# Switched_I2C.net
KiCad netlist of a schematic drawn in EAGLE
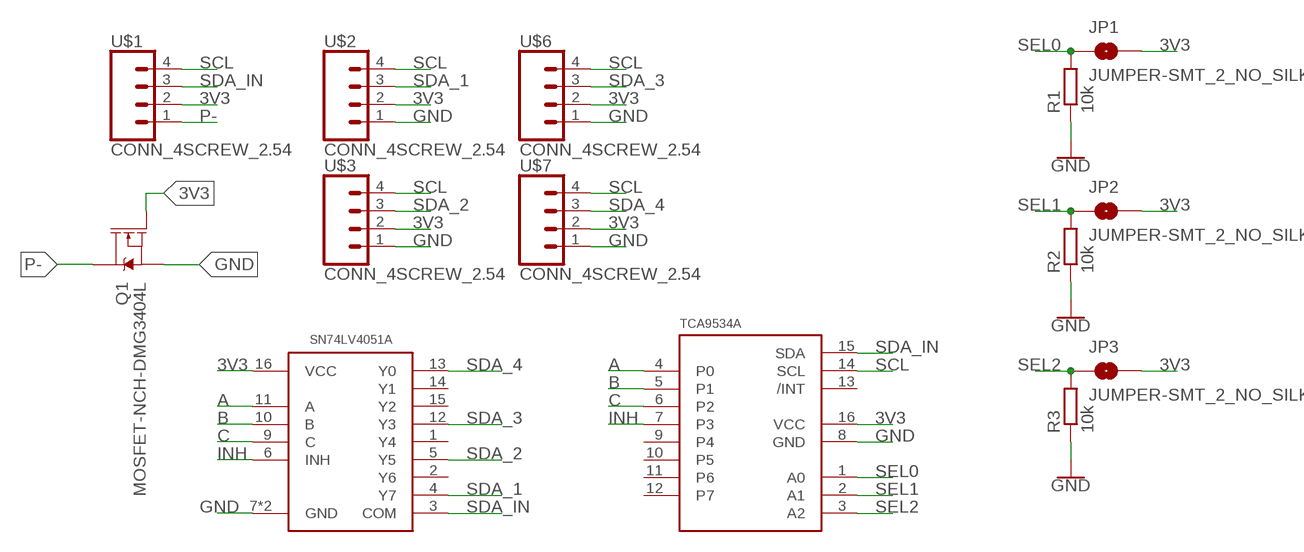
[diagram p0: schematic, sheet 1]

(export (version "E")
  (design (tool "Eeschema 10.0.6"))
  (components
    (comp (ref "JP1")
      (value "JUMPER-SMT_2_NO_SILK")
      (footprint "eagle-import:SMT-JUMPER_2_NO_SILK")
      (libsource (lib "eagle-import") (part "JUMPER-SMT_2_NO_SILK"))
    )
    (comp (ref "JP2")
      (value "JUMPER-SMT_2_NO_SILK")
      (footprint "eagle-import:SMT-JUMPER_2_NO_SILK")
      (libsource (lib "eagle-import") (part "JUMPER-SMT_2_NO_SILK"))
    )
    (comp (ref "JP3")
      (value "JUMPER-SMT_2_NO_SILK")
      (footprint "eagle-import:SMT-JUMPER_2_NO_SILK")
      (libsource (lib "eagle-import") (part "JUMPER-SMT_2_NO_SILK"))
    )
    (comp (ref "Q1")
      (value "MOSFET-NCH-DMG3404L")
      (footprint "eagle-import:SOT23-3")
      (libsource (lib "eagle-import") (part "MOSFET-NCH-DMG3404L"))
    )
    (comp (ref "R1")
      (value "10k")
      (footprint "eagle-import:R0603")
      (libsource (lib "eagle-import") (part "R-EU_R0603"))
    )
    (comp (ref "R2")
      (value "10k")
      (footprint "eagle-import:R0603")
      (libsource (lib "eagle-import") (part "R-EU_R0603"))
    )
    (comp (ref "R3")
      (value "10k")
      (footprint "eagle-import:R0603")
      (libsource (lib "eagle-import") (part "R-EU_R0603"))
    )
    (comp (ref "U$1")
      (value "CONN_4SCREW_2.54")
      (footprint "eagle-import:1X04")
      (libsource (lib "eagle-import") (part "CONN_4SCREW_2.54"))
    )
    (comp (ref "U$2")
      (value "CONN_4SCREW_2.54")
      (footprint "eagle-import:1X04")
      (libsource (lib "eagle-import") (part "CONN_4SCREW_2.54"))
    )
    (comp (ref "U$3")
      (value "CONN_4SCREW_2.54")
      (footprint "eagle-import:1X04")
      (libsource (lib "eagle-import") (part "CONN_4SCREW_2.54"))
    )
    (comp (ref "U$5")
      (value "SN74LV4051ATSSOP")
      (footprint "eagle-import:TSSOP16")
      (fields (field (name "MF") "TI") (field (name "MPN") "SN74LV4051APWRG4"))
      (libsource (lib "eagle-import") (part "SN74LV4051ATSSOP"))
    )
    (comp (ref "U$6")
      (value "CONN_4SCREW_2.54")
      (footprint "eagle-import:1X04")
      (libsource (lib "eagle-import") (part "CONN_4SCREW_2.54"))
    )
    (comp (ref "U$7")
      (value "CONN_4SCREW_2.54")
      (footprint "eagle-import:1X04")
      (libsource (lib "eagle-import") (part "CONN_4SCREW_2.54"))
    )
    (comp (ref "U$8")
      (value "TCA9534A")
      (footprint "eagle-import:TSSOP16")
      (libsource (lib "eagle-import") (part "TCA9534A"))
    )
  )
  (nets
    (net (code "1") (name "/A") (class "Default")
      (node (ref "U$5") (pin "11") (pinfunction "A_11") (pintype "bidirectional"))
      (node (ref "U$8") (pin "4") (pinfunction "P0_4") (pintype "bidirectional"))
    )
    (net (code "2") (name "/B") (class "Default")
      (node (ref "U$5") (pin "10") (pinfunction "B_10") (pintype "bidirectional"))
      (node (ref "U$8") (pin "5") (pinfunction "P1_5") (pintype "bidirectional"))
    )
    (net (code "3") (name "/C") (class "Default")
      (node (ref "U$5") (pin "9") (pinfunction "C_9") (pintype "bidirectional"))
      (node (ref "U$8") (pin "6") (pinfunction "P2_6") (pintype "bidirectional"))
    )
    (net (code "4") (name "/INH") (class "Default")
      (node (ref "U$5") (pin "6") (pinfunction "INH_6") (pintype "bidirectional"))
      (node (ref "U$8") (pin "7") (pinfunction "P3_7") (pintype "bidirectional"))
    )
    (net (code "5") (name "/SCL") (class "Default")
      (node (ref "U$1") (pin "4") (pinfunction "4_4") (pintype "passive"))
      (node (ref "U$2") (pin "4") (pinfunction "4_4") (pintype "passive"))
      (node (ref "U$3") (pin "4") (pinfunction "4_4") (pintype "passive"))
      (node (ref "U$6") (pin "4") (pinfunction "4_4") (pintype "passive"))
      (node (ref "U$7") (pin "4") (pinfunction "4_4") (pintype "passive"))
      (node (ref "U$8") (pin "14") (pinfunction "SCL_14") (pintype "bidirectional"))
    )
    (net (code "6") (name "/SDA_1") (class "Default")
      (node (ref "U$2") (pin "3") (pinfunction "3_3") (pintype "passive"))
      (node (ref "U$5") (pin "4") (pinfunction "Y7_4") (pintype "bidirectional"))
    )
    (net (code "7") (name "/SDA_2") (class "Default")
      (node (ref "U$3") (pin "3") (pinfunction "3_3") (pintype "passive"))
      (node (ref "U$5") (pin "5") (pinfunction "Y5_5") (pintype "bidirectional"))
    )
    (net (code "8") (name "/SDA_3") (class "Default")
      (node (ref "U$5") (pin "12") (pinfunction "Y3_12") (pintype "bidirectional"))
      (node (ref "U$6") (pin "3") (pinfunction "3_3") (pintype "passive"))
    )
    (net (code "9") (name "/SDA_4") (class "Default")
      (node (ref "U$5") (pin "13") (pinfunction "Y0_13") (pintype "bidirectional"))
      (node (ref "U$7") (pin "3") (pinfunction "3_3") (pintype "passive"))
    )
    (net (code "10") (name "/SDA_IN") (class "Default")
      (node (ref "U$1") (pin "3") (pinfunction "3_3") (pintype "passive"))
      (node (ref "U$5") (pin "3") (pinfunction "COM_3") (pintype "bidirectional"))
      (node (ref "U$8") (pin "15") (pinfunction "SDA_15") (pintype "bidirectional"))
    )
    (net (code "11") (name "/SEL0") (class "Default")
      (node (ref "JP1") (pin "1") (pinfunction "1_1") (pintype "passive"))
      (node (ref "R1") (pin "2") (pinfunction "2_2") (pintype "passive"))
      (node (ref "U$8") (pin "1") (pinfunction "A0_1") (pintype "input"))
    )
    (net (code "12") (name "/SEL1") (class "Default")
      (node (ref "JP2") (pin "1") (pinfunction "1_1") (pintype "passive"))
      (node (ref "R2") (pin "2") (pinfunction "2_2") (pintype "passive"))
      (node (ref "U$8") (pin "2") (pinfunction "A1_2") (pintype "input"))
    )
    (net (code "13") (name "/SEL2") (class "Default")
      (node (ref "JP3") (pin "1") (pinfunction "1_1") (pintype "passive"))
      (node (ref "R3") (pin "2") (pinfunction "2_2") (pintype "passive"))
      (node (ref "U$8") (pin "3") (pinfunction "A2_3") (pintype "input"))
    )
    (net (code "14") (name "3V3") (class "Default")
      (node (ref "JP1") (pin "2") (pinfunction "2_2") (pintype "passive"))
      (node (ref "JP2") (pin "2") (pinfunction "2_2") (pintype "passive"))
      (node (ref "JP3") (pin "2") (pinfunction "2_2") (pintype "passive"))
      (node (ref "Q1") (pin "1") (pinfunction "G_1") (pintype "bidirectional"))
      (node (ref "U$1") (pin "2") (pinfunction "2_2") (pintype "passive"))
      (node (ref "U$2") (pin "2") (pinfunction "2_2") (pintype "passive"))
      (node (ref "U$3") (pin "2") (pinfunction "2_2") (pintype "passive"))
      (node (ref "U$5") (pin "16") (pinfunction "VCC_16") (pintype "bidirectional"))
      (node (ref "U$6") (pin "2") (pinfunction "2_2") (pintype "passive"))
      (node (ref "U$7") (pin "2") (pinfunction "2_2") (pintype "passive"))
      (node (ref "U$8") (pin "16") (pinfunction "VCC_16") (pintype "power_in"))
    )
    (net (code "15") (name "GND") (class "Default")
      (node (ref "Q1") (pin "2") (pinfunction "S_2") (pintype "bidirectional"))
      (node (ref "R1") (pin "1") (pinfunction "1_1") (pintype "passive"))
      (node (ref "R2") (pin "1") (pinfunction "1_1") (pintype "passive"))
      (node (ref "R3") (pin "1") (pinfunction "1_1") (pintype "passive"))
      (node (ref "U$2") (pin "1") (pinfunction "1_1") (pintype "passive"))
      (node (ref "U$3") (pin "1") (pinfunction "1_1") (pintype "passive"))
      (node (ref "U$5") (pin "7") (pinfunction "GND_7") (pintype "bidirectional"))
      (node (ref "U$5") (pin "8") (pinfunction "GND_8") (pintype "bidirectional"))
      (node (ref "U$6") (pin "1") (pinfunction "1_1") (pintype "passive"))
      (node (ref "U$7") (pin "1") (pinfunction "1_1") (pintype "passive"))
      (node (ref "U$8") (pin "8") (pinfunction "GND_8") (pintype "power_in"))
    )
    (net (code "16") (name "P-") (class "Default")
      (node (ref "Q1") (pin "3") (pinfunction "D_3") (pintype "bidirectional"))
      (node (ref "U$1") (pin "1") (pinfunction "1_1") (pintype "passive"))
    )
    (net (code "17") (name "unconnected-(U$5-Y1-Pad14)") (class "Default")
      (node (ref "U$5") (pin "14") (pinfunction "Y1_14") (pintype "bidirectional"))
    )
    (net (code "18") (name "unconnected-(U$5-Y2-Pad15)") (class "Default")
      (node (ref "U$5") (pin "15") (pinfunction "Y2_15") (pintype "bidirectional"))
    )
    (net (code "19") (name "unconnected-(U$5-Y4-Pad1)") (class "Default")
      (node (ref "U$5") (pin "1") (pinfunction "Y4_1") (pintype "bidirectional"))
    )
    (net (code "20") (name "unconnected-(U$5-Y6-Pad2)") (class "Default")
      (node (ref "U$5") (pin "2") (pinfunction "Y6_2") (pintype "bidirectional"))
    )
    (net (code "21") (name "unconnected-(U$8-P4-Pad9)") (class "Default")
      (node (ref "U$8") (pin "9") (pinfunction "P4_9") (pintype "bidirectional"))
    )
    (net (code "22") (name "unconnected-(U$8-P5-Pad10)") (class "Default")
      (node (ref "U$8") (pin "10") (pinfunction "P5_10") (pintype "bidirectional"))
    )
    (net (code "23") (name "unconnected-(U$8-P6-Pad11)") (class "Default")
      (node (ref "U$8") (pin "11") (pinfunction "P6_11") (pintype "bidirectional"))
    )
    (net (code "24") (name "unconnected-(U$8-P7-Pad12)") (class "Default")
      (node (ref "U$8") (pin "12") (pinfunction "P7_12") (pintype "bidirectional"))
    )
    (net (code "25") (name "unconnected-(U$8-{slash}INT-Pad13)") (class "Default")
      (node (ref "U$8") (pin "13") (pinfunction "/INT_13") (pintype "output"))
    )
  )
)
